# MCU.net
KiCad netlist of a schematic drawn in Altium Designer
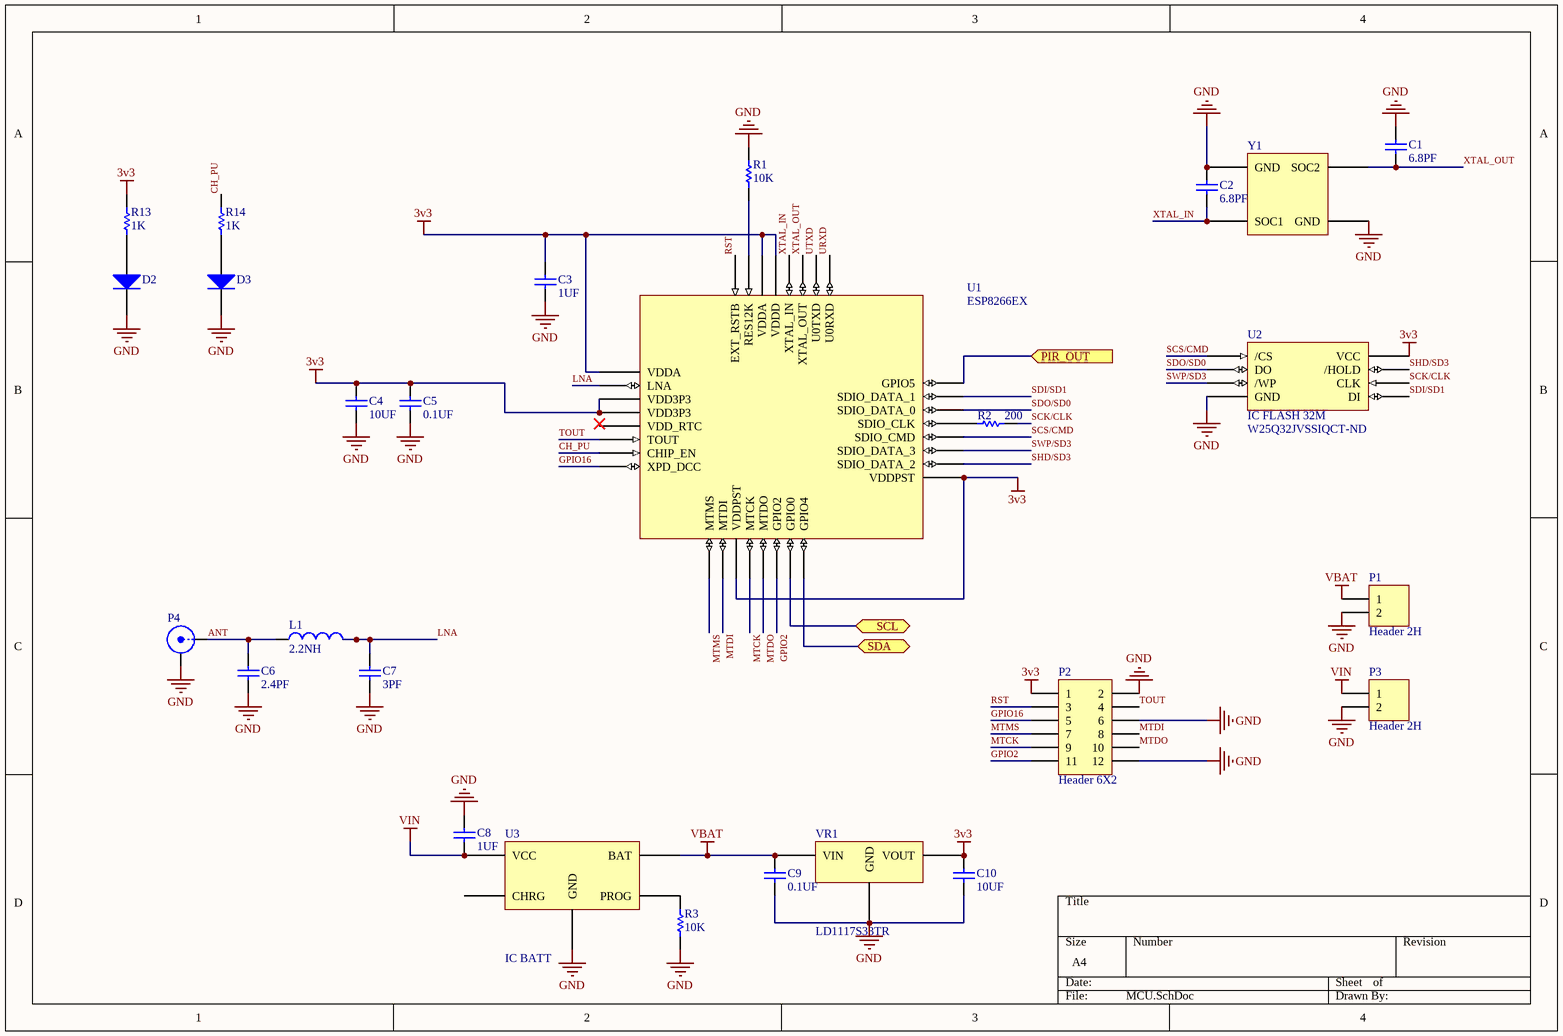
[diagram p0: MCU.SchDoc]

(export (version "E")
  (design (tool "Eeschema 10.0.6"))
  (components
    (comp (ref "C1")
      (value "6.8PF")
      (footprint "Chip2PinSM127P600-8N-SAMSUNG-0603")
      (description "CAP CER 6.8PF 50V C0G/NP0 0603")
      (fields
        (field (name "MANUFACTURER") "Samsung Electro-Mechanics")
        (field (name "MANUFACTURER PART NUMBER") "CL10C6R8DB8NNNC")
      )
      (libsource (lib "Schlib1") (part "CL10C6R8DB8NNNC"))
    )
    (comp (ref "C2")
      (value "6.8PF")
      (footprint "Chip2PinSM127P600-8N-SAMSUNG-0603")
      (description "CAP CER 6.8PF 50V C0G/NP0 0603")
      (fields
        (field (name "MANUFACTURER") "Samsung Electro-Mechanics")
        (field (name "MANUFACTURER PART NUMBER") "CL10C6R8DB8NNNC")
      )
      (libsource (lib "Schlib1") (part "CL10C6R8DB8NNNC"))
    )
    (comp (ref "C3")
      (value "1UF")
      (footprint "Chip2PinSM127P600-8N-SAMSUNG-0603")
      (description "CAP CER 1UF 10V X7R 0603")
      (fields
        (field (name "MANUFACTURER") "Samsung Electro-Mechanics")
        (field (name "MANUFACTURER PART NUMBER") "CL10B105KP8NNNC")
      )
      (libsource (lib "Schlib1") (part "CL10B105KP8NNNC"))
    )
    (comp (ref "C4")
      (value "10UF")
      (footprint "Chip2PinSM127P600-8N-SAMSUNG-0603")
      (description "CAP CER 10UF 6.3V X5R 0603")
      (fields
        (field (name "MANUFACTURER") "Samsung Electro-Mechanics")
        (field (name "MANUFACTURER PART NUMBER") "CL10A106KQ8NNNC")
      )
      (libsource (lib "Schlib1") (part "CL10A106KQ8NNNC"))
    )
    (comp (ref "C5")
      (value "0.1UF")
      (footprint "Chip2PinSM127P600-8N-SAMSUNG-0603")
      (description "CAP CER 0.1UF 16V Y5V 0603")
      (fields
        (field (name "MANUFACTURER") "Samsung Electro-Mechanics")
        (field (name "MANUFACTURER PART NUMBER") "CL10F104ZO8NNNC")
      )
      (libsource (lib "Schlib1") (part "CL10F104ZO8NNNC"))
    )
    (comp (ref "C6")
      (value "2.4PF")
      (footprint "Chip2PinSM127P600-8N-SAMSUNG-0603")
      (description "CAP CER 2.4PF 50V C0G/NP0 0603")
      (fields
        (field (name "MANUFACTURER") "Samsung Electro-Mechanics")
        (field (name "MANUFACTURER PART NUMBER") "CL10C2R4BB8NNNC")
      )
      (libsource (lib "Schlib1") (part "CL10C2R4BB8NNNC"))
    )
    (comp (ref "C7")
      (value "3PF")
      (footprint "Chip2PinSM127P600-8N-TDK_0603")
      (description "CAP CER 3PF 50V C0G/NP0 0603")
      (fields
        (field (name "MANUFACTURER") "Samsung Electro-Mechanics")
        (field (name "MANUFACTURER PART NUMBER") "CL10C030BB8NNNC")
      )
      (libsource (lib "Schlib1") (part "CL10C030BB8NNNC"))
    )
    (comp (ref "C8")
      (value "1UF")
      (footprint "Chip2PinSM127P600-8N-SAMSUNG-0603")
      (description "CAP CER 1UF 10V X7R 0603")
      (fields
        (field (name "MANUFACTURER") "Samsung Electro-Mechanics")
        (field (name "MANUFACTURER PART NUMBER") "CL10B105KP8NNNC")
      )
      (libsource (lib "Schlib1") (part "CL10B105KP8NNNC"))
    )
    (comp (ref "C9")
      (value "0.1UF")
      (footprint "Chip2PinSM127P600-8N-SAMSUNG-0603")
      (description "CAP CER 0.1UF 16V Y5V 0603")
      (fields
        (field (name "MANUFACTURER") "Samsung Electro-Mechanics")
        (field (name "MANUFACTURER PART NUMBER") "CL10F104ZO8NNNC")
      )
      (libsource (lib "Schlib1") (part "CL10F104ZO8NNNC"))
    )
    (comp (ref "C10")
      (value "10UF")
      (footprint "Chip2PinSM127P600-8N-SAMSUNG-0603")
      (description "CAP CER 10UF 6.3V X5R 0603")
      (fields
        (field (name "MANUFACTURER") "Samsung Electro-Mechanics")
        (field (name "MANUFACTURER PART NUMBER") "CL10A106KQ8NNNC")
      )
      (libsource (lib "Schlib1") (part "CL10A106KQ8NNNC"))
    )
    (comp (ref "D2")
      (value "SML-D12M8WT86")
      (footprint "LED_0603_ROHM")
      (description "LED GREEN DIFFUSED 0603 SMD")
      (fields (field (name "MANUFACTURER") "Rohm Semiconductor") (field (name "BASE PART NUMBER") "SML-D12"))
      (libsource (lib "Schlib1") (part "SML-D12M8WT86"))
    )
    (comp (ref "D3")
      (value "SML-D12M8WT86")
      (footprint "LED_0603_ROHM")
      (description "LED GREEN DIFFUSED 0603 SMD")
      (fields (field (name "MANUFACTURER") "Rohm Semiconductor") (field (name "BASE PART NUMBER") "SML-D12"))
      (libsource (lib "Schlib1") (part "SML-D12M8WT86"))
    )
    (comp (ref "L1")
      (value "2.2NH")
      (footprint "Chip2PinSM127P600-8N-SAMSUNG-0603")
      (description "FIXED IND 2.2NH 300MA 150 MOHM")
      (fields
        (field (name "MANUFACTURER") "Johanson Technology Inc.")
        (field (name "MANUFACTURER PART NUMBER") "L-14C2N2SV4T")
      )
      (libsource (lib "Schlib1") (part "L-14C2N2SV4T"))
    )
    (comp (ref "P1")
      (value "Header 2H")
      (footprint "PCBComponent_1 - duplicate")
      (description "Header, 2-Pin, Right Angle")
      (fields (field (name "PUBLISHER") "Altium Limited"))
      (libsource (lib "Miscellaneous Connectors") (part "Header 2H"))
    )
    (comp (ref "P2")
      (value "Header 6X2")
      (footprint "HDR2X6")
      (description "Header, 6-Pin, Dual row")
      (fields (field (name "PUBLISHER") "Altium Limited"))
      (libsource (lib "Miscellaneous Connectors") (part "Header 6X2"))
    )
    (comp (ref "P3")
      (value "Header 2H")
      (footprint "PCBComponent_1 - duplicate")
      (description "Header, 2-Pin, Right Angle")
      (fields (field (name "PUBLISHER") "Altium Limited"))
      (libsource (lib "Miscellaneous Connectors") (part "Header 2H"))
    )
    (comp (ref "P4")
      (value "~")
      (footprint "PCBComponent_1 - duplicate3")
      (description "SMB Straight Connector")
      (fields (field (name "PUBLISHER") "Altium Limited"))
      (libsource (lib "Miscellaneous Connectors") (part "SMB"))
    )
    (comp (ref "R1")
      (value "10K")
      (footprint "Chip2PinSM127P600-8N-vishay-0603")
      (description "RES SMD 10K OHM 1% 1/8W 0603")
      (fields
        (field (name "MANUFACTURER") "Vishay Beyschlag")
        (field (name "MANUFACTURER PART NUMBER") "MCT06030C1002FP500")
      )
      (libsource (lib "Schlib1") (part "MCT06030C1002FP500"))
    )
    (comp (ref "R2")
      (value "200")
      (footprint "Chip2PinSM127P600-8N-SAMSUNG-0603")
      (description "RES SMD 200 OHM 1% 1/10W 0603")
      (fields
        (field (name "MANUFACTURER") "Samsung Electro-Mechanics")
        (field (name "MANUFACTURER PART NUMBER") "RC1608F201CS")
      )
      (libsource (lib "Schlib1") (part "RC1608F201CS"))
    )
    (comp (ref "R3")
      (value "10K")
      (footprint "Chip2PinSM127P600-8N-vishay-0603")
      (description "RES SMD 10K OHM 1% 1/8W 0603")
      (fields
        (field (name "MANUFACTURER") "Vishay Beyschlag")
        (field (name "MANUFACTURER PART NUMBER") "MCT06030C1002FP500")
      )
      (libsource (lib "Schlib1") (part "MCT06030C1002FP500"))
    )
    (comp (ref "R13")
      (value "1K")
      (footprint "Chip2PinSM127P600-8N-vishay-0603")
      (description "RES SMD 1K OHM 1% 1/8W 0603")
      (fields
        (field (name "MANUFACTURER") "Vishay Beyschlag")
        (field (name "MANUFACTURER PART NUMBER") "MCT06030C1001FP500")
      )
      (libsource (lib "Schlib1") (part "MCT06030C1001FP500"))
    )
    (comp (ref "R14")
      (value "1K")
      (footprint "Chip2PinSM127P600-8N-vishay-0603")
      (description "RES SMD 1K OHM 1% 1/8W 0603")
      (fields
        (field (name "MANUFACTURER") "Vishay Beyschlag")
        (field (name "MANUFACTURER PART NUMBER") "MCT06030C1001FP500")
      )
      (libsource (lib "Schlib1") (part "MCT06030C1001FP500"))
    )
    (comp (ref "U1")
      (value "ESP8266EX")
      (footprint "QFN127P600-8N")
      (description "SMD IC ESP8266EX, QFN32-PIN, 5_5")
      (fields (field (name "MANUFACTURER") "Espressif Systems"))
      (libsource (lib "Schlib1") (part "ESP8266EX"))
    )
    (comp (ref "U2")
      (value "IC FLASH 32M")
      (footprint "SOIC127P600-8N-208")
      (description "IC FLASH 32M SPI 133MHZ 8SOIC")
      (fields
        (field (name "MANUFACTURER") "Winbond Electronics")
        (field (name "MANUFACTURER PART NUMBER") "W25Q32JVSSIQ TR")
        (field (name "SUPPLIER PART NUMBER 1") "W25Q32JVSSIQCT-ND")
      )
      (libsource (lib "Schlib1") (part "W25Q32JVSSIQ TR"))
    )
    (comp (ref "U3")
      (value "IC BATT")
      (footprint "SOT23127P600-8N-STC4054")
      (description "IC BATT CHRGR 800MA TSOT23-5")
      (fields
        (field (name "MANUFACTURER") "STMicroelectronics")
        (field (name "MANUFACTURER PART NUMBER") "STC4054GR")
      )
      (libsource (lib "Schlib1") (part "STC4054GR"))
    )
    (comp (ref "VR1")
      (value "LD1117S33TR")
      (footprint "SOT230P700X180-4N_ST")
      (description "IC REG LINEAR 3.3V 800MA SOT223")
      (fields (field (name "MANUFACTURER") "STMicroelectronics") (field (name "BASE PART NUMBER") "LD1117"))
      (libsource (lib "Schlib1") (part "LD1117S33TR"))
    )
    (comp (ref "Y1")
      (value "FA-128 26.0000MF10Z-W5")
      (footprint "PCBComponent_1")
      (description "CRYSTAL 26.0000MHZ 12PF SMD")
      (fields (field (name "MANUFACTURER") "EPSON"))
      (libsource (lib "Schlib1") (part "FA-128 26.0000MF10Z-W5"))
    )
  )
  (nets
    (net (code "1") (name "/ANT") (class "Default")
      (node (ref "C6") (pin "1") (pinfunction "1_1") (pintype "passive"))
      (node (ref "L1") (pin "1") (pinfunction "1_1") (pintype "passive"))
      (node (ref "P4") (pin "1") (pinfunction "X_1") (pintype "passive"))
    )
    (net (code "2") (name "/CH_PU") (class "Default")
      (node (ref "R14") (pin "2") (pinfunction "2_2") (pintype "passive"))
      (node (ref "U1") (pin "7") (pinfunction "CHIP_EN_7") (pintype "input"))
    )
    (net (code "3") (name "/GPIO2") (class "Default")
      (node (ref "P2") (pin "11") (pinfunction "11_11") (pintype "passive"))
      (node (ref "U1") (pin "14") (pinfunction "GPIO2_14") (pintype "bidirectional"))
    )
    (net (code "4") (name "/GPIO16") (class "Default")
      (node (ref "P2") (pin "5") (pinfunction "5_5") (pintype "passive"))
      (node (ref "U1") (pin "8") (pinfunction "XPD_DCC_8") (pintype "bidirectional"))
    )
    (net (code "5") (name "/LNA") (class "Default")
      (node (ref "C7") (pin "1") (pinfunction "1_1") (pintype "passive"))
      (node (ref "L1") (pin "2") (pinfunction "2_2") (pintype "passive"))
      (node (ref "U1") (pin "2") (pinfunction "LNA_2") (pintype "bidirectional"))
    )
    (net (code "6") (name "/MTCK") (class "Default")
      (node (ref "P2") (pin "9") (pinfunction "9_9") (pintype "passive"))
      (node (ref "U1") (pin "12") (pinfunction "MTCK_12") (pintype "bidirectional"))
    )
    (net (code "7") (name "/MTDI") (class "Default")
      (node (ref "P2") (pin "8") (pinfunction "8_8") (pintype "passive"))
      (node (ref "U1") (pin "10") (pinfunction "MTDI_10") (pintype "bidirectional"))
    )
    (net (code "8") (name "/MTDO") (class "Default")
      (node (ref "P2") (pin "10") (pinfunction "10_10") (pintype "passive"))
      (node (ref "U1") (pin "13") (pinfunction "MTDO_13") (pintype "bidirectional"))
    )
    (net (code "9") (name "/MTMS") (class "Default")
      (node (ref "P2") (pin "7") (pinfunction "7_7") (pintype "passive"))
      (node (ref "U1") (pin "9") (pinfunction "MTMS_9") (pintype "bidirectional"))
    )
    (net (code "10") (name "/PIR_OUT") (class "Default")
      (node (ref "U1") (pin "24") (pinfunction "GPIO5_24") (pintype "bidirectional"))
    )
    (net (code "11") (name "/RST") (class "Default")
      (node (ref "P2") (pin "3") (pinfunction "3_3") (pintype "passive"))
      (node (ref "U1") (pin "32") (pinfunction "EXT_RSTB_32") (pintype "input"))
    )
    (net (code "12") (name "/SCK{slash}CLK") (class "Default")
      (node (ref "R2") (pin "2") (pinfunction "2_2") (pintype "passive"))
      (node (ref "U2") (pin "6") (pinfunction "CLK_6") (pintype "input"))
    )
    (net (code "13") (name "/SCL") (class "Default")
      (node (ref "U1") (pin "15") (pinfunction "GPIO0_15") (pintype "bidirectional"))
    )
    (net (code "14") (name "/SCS{slash}CMD") (class "Default")
      (node (ref "U1") (pin "20") (pinfunction "SDIO_CMD_20") (pintype "bidirectional"))
      (node (ref "U2") (pin "1") (pinfunction "/CS_1") (pintype "input"))
    )
    (net (code "15") (name "/SDA") (class "Default")
      (node (ref "U1") (pin "16") (pinfunction "GPIO4_16") (pintype "bidirectional"))
    )
    (net (code "16") (name "/SDI{slash}SD1") (class "Default")
      (node (ref "U1") (pin "23") (pinfunction "SDIO_DATA_1_23") (pintype "bidirectional"))
      (node (ref "U2") (pin "5") (pinfunction "DI_5") (pintype "bidirectional"))
    )
    (net (code "17") (name "/SDO{slash}SD0") (class "Default")
      (node (ref "U1") (pin "22") (pinfunction "SDIO_DATA_0_22") (pintype "bidirectional"))
      (node (ref "U2") (pin "2") (pinfunction "DO_2") (pintype "bidirectional"))
    )
    (net (code "18") (name "/SHD{slash}SD3") (class "Default")
      (node (ref "U1") (pin "18") (pinfunction "SDIO_DATA_2_18") (pintype "bidirectional"))
      (node (ref "U2") (pin "7") (pinfunction "/HOLD_7") (pintype "bidirectional"))
    )
    (net (code "19") (name "/SWP{slash}SD3") (class "Default")
      (node (ref "U1") (pin "19") (pinfunction "SDIO_DATA_3_19") (pintype "bidirectional"))
      (node (ref "U2") (pin "3") (pinfunction "/WP_3") (pintype "bidirectional"))
    )
    (net (code "20") (name "/TOUT") (class "Default")
      (node (ref "P2") (pin "4") (pinfunction "4_4") (pintype "passive"))
      (node (ref "U1") (pin "6") (pinfunction "TOUT_6") (pintype "input"))
    )
    (net (code "21") (name "/URXD") (class "Default")
      (node (ref "U1") (pin "25") (pinfunction "U0RXD_25") (pintype "bidirectional"))
    )
    (net (code "22") (name "/UTXD") (class "Default")
      (node (ref "U1") (pin "26") (pinfunction "U0TXD_26") (pintype "bidirectional"))
    )
    (net (code "23") (name "/XTAL_IN") (class "Default")
      (node (ref "C2") (pin "1") (pinfunction "1_1") (pintype "passive"))
      (node (ref "U1") (pin "28") (pinfunction "XTAL_IN_28") (pintype "bidirectional"))
      (node (ref "Y1") (pin "1") (pinfunction "SOC1_1") (pintype "power_in"))
    )
    (net (code "24") (name "/XTAL_OUT") (class "Default")
      (node (ref "C1") (pin "1") (pinfunction "1_1") (pintype "passive"))
      (node (ref "U1") (pin "27") (pinfunction "XTAL_OUT_27") (pintype "bidirectional"))
      (node (ref "Y1") (pin "3") (pinfunction "SOC2_3") (pintype "passive"))
    )
    (net (code "25") (name "3v3") (class "Default")
      (node (ref "C10") (pin "1") (pinfunction "1_1") (pintype "passive"))
      (node (ref "C3") (pin "1") (pinfunction "1_1") (pintype "passive"))
      (node (ref "C4") (pin "1") (pinfunction "1_1") (pintype "passive"))
      (node (ref "C5") (pin "2") (pinfunction "2_2") (pintype "passive"))
      (node (ref "P2") (pin "1") (pinfunction "1_1") (pintype "passive"))
      (node (ref "R13") (pin "2") (pinfunction "2_2") (pintype "passive"))
      (node (ref "U1") (pin "1") (pinfunction "VDDA_1") (pintype "power_in"))
      (node (ref "U1") (pin "11") (pinfunction "VDDPST_11") (pintype "power_in"))
      (node (ref "U1") (pin "17") (pinfunction "VDDPST_17") (pintype "power_in"))
      (node (ref "U1") (pin "29") (pinfunction "VDDD_29") (pintype "power_in"))
      (node (ref "U1") (pin "3") (pinfunction "VDD3P3_3") (pintype "power_in"))
      (node (ref "U1") (pin "30") (pinfunction "VDDA_30") (pintype "power_in"))
      (node (ref "U1") (pin "4") (pinfunction "VDD3P3_4") (pintype "power_in"))
      (node (ref "U2") (pin "8") (pinfunction "VCC_8") (pintype "power_in"))
      (node (ref "VR1") (pin "2") (pinfunction "VOUT_2") (pintype "power_in"))
    )
    (net (code "26") (name "GND") (class "Default")
      (node (ref "C1") (pin "2") (pinfunction "2_2") (pintype "passive"))
      (node (ref "C10") (pin "2") (pinfunction "2_2") (pintype "passive"))
      (node (ref "C2") (pin "2") (pinfunction "2_2") (pintype "passive"))
      (node (ref "C3") (pin "2") (pinfunction "2_2") (pintype "passive"))
      (node (ref "C4") (pin "2") (pinfunction "2_2") (pintype "passive"))
      (node (ref "C5") (pin "1") (pinfunction "1_1") (pintype "passive"))
      (node (ref "C6") (pin "2") (pinfunction "2_2") (pintype "passive"))
      (node (ref "C7") (pin "2") (pinfunction "2_2") (pintype "passive"))
      (node (ref "C8") (pin "2") (pinfunction "2_2") (pintype "passive"))
      (node (ref "C9") (pin "2") (pinfunction "2_2") (pintype "passive"))
      (node (ref "D2") (pin "2") (pinfunction "K_2") (pintype "passive"))
      (node (ref "D3") (pin "2") (pinfunction "K_2") (pintype "passive"))
      (node (ref "P1") (pin "2") (pinfunction "2_2") (pintype "passive"))
      (node (ref "P2") (pin "12") (pinfunction "12_12") (pintype "passive"))
      (node (ref "P2") (pin "2") (pinfunction "2_2") (pintype "passive"))
      (node (ref "P2") (pin "6") (pinfunction "6_6") (pintype "passive"))
      (node (ref "P3") (pin "2") (pinfunction "2_2") (pintype "passive"))
      (node (ref "P4") (pin "2") (pinfunction "Y_2") (pintype "passive"))
      (node (ref "R1") (pin "2") (pinfunction "2_2") (pintype "passive"))
      (node (ref "R3") (pin "2") (pinfunction "2_2") (pintype "passive"))
      (node (ref "U2") (pin "4") (pinfunction "GND_4") (pintype "power_in"))
      (node (ref "U3") (pin "2") (pinfunction "GND_2") (pintype "power_in"))
      (node (ref "VR1") (pin "1") (pinfunction "GND_1") (pintype "power_in"))
      (node (ref "Y1") (pin "2") (pinfunction "GND_2") (pintype "power_in"))
      (node (ref "Y1") (pin "4") (pinfunction "GND_4") (pintype "passive"))
    )
    (net (code "27") (name "Net-(D2-A)") (class "Default")
      (node (ref "D2") (pin "1") (pinfunction "A_1") (pintype "passive"))
      (node (ref "R13") (pin "1") (pinfunction "1_1") (pintype "passive"))
    )
    (net (code "28") (name "Net-(D3-A)") (class "Default")
      (node (ref "D3") (pin "1") (pinfunction "A_1") (pintype "passive"))
      (node (ref "R14") (pin "1") (pinfunction "1_1") (pintype "passive"))
    )
    (net (code "29") (name "Net-(U1-RES12K)") (class "Default")
      (node (ref "R1") (pin "1") (pinfunction "1_1") (pintype "passive"))
      (node (ref "U1") (pin "31") (pinfunction "RES12K_31") (pintype "input"))
    )
    (net (code "30") (name "Net-(U1-SDIO_CLK)") (class "Default")
      (node (ref "R2") (pin "1") (pinfunction "1_1") (pintype "passive"))
      (node (ref "U1") (pin "21") (pinfunction "SDIO_CLK_21") (pintype "bidirectional"))
    )
    (net (code "31") (name "Net-(U3-PROG)") (class "Default")
      (node (ref "R3") (pin "1") (pinfunction "1_1") (pintype "passive"))
      (node (ref "U3") (pin "5") (pinfunction "PROG_5") (pintype "power_in"))
    )
    (net (code "32") (name "VBAT") (class "Default")
      (node (ref "C9") (pin "1") (pinfunction "1_1") (pintype "passive"))
      (node (ref "P1") (pin "1") (pinfunction "1_1") (pintype "passive"))
      (node (ref "U3") (pin "3") (pinfunction "BAT_3") (pintype "power_in"))
      (node (ref "VR1") (pin "3") (pinfunction "VIN_3") (pintype "power_in"))
    )
    (net (code "33") (name "VIN") (class "Default")
      (node (ref "C8") (pin "1") (pinfunction "1_1") (pintype "passive"))
      (node (ref "P3") (pin "1") (pinfunction "1_1") (pintype "passive"))
      (node (ref "U3") (pin "4") (pinfunction "VCC_4") (pintype "power_in"))
    )
    (net (code "34") (name "unconnected-(U1-VDD_RTC-Pad5)") (class "Default")
      (node (ref "U1") (pin "5") (pinfunction "VDD_RTC_5") (pintype "power_in"))
    )
    (net (code "35") (name "unconnected-(U3-CHRG-Pad1)") (class "Default")
      (node (ref "U3") (pin "1") (pinfunction "CHRG_1") (pintype "power_in"))
    )
  )
)
